# updateMate.net
KiCad netlist of a schematic drawn in EAGLE
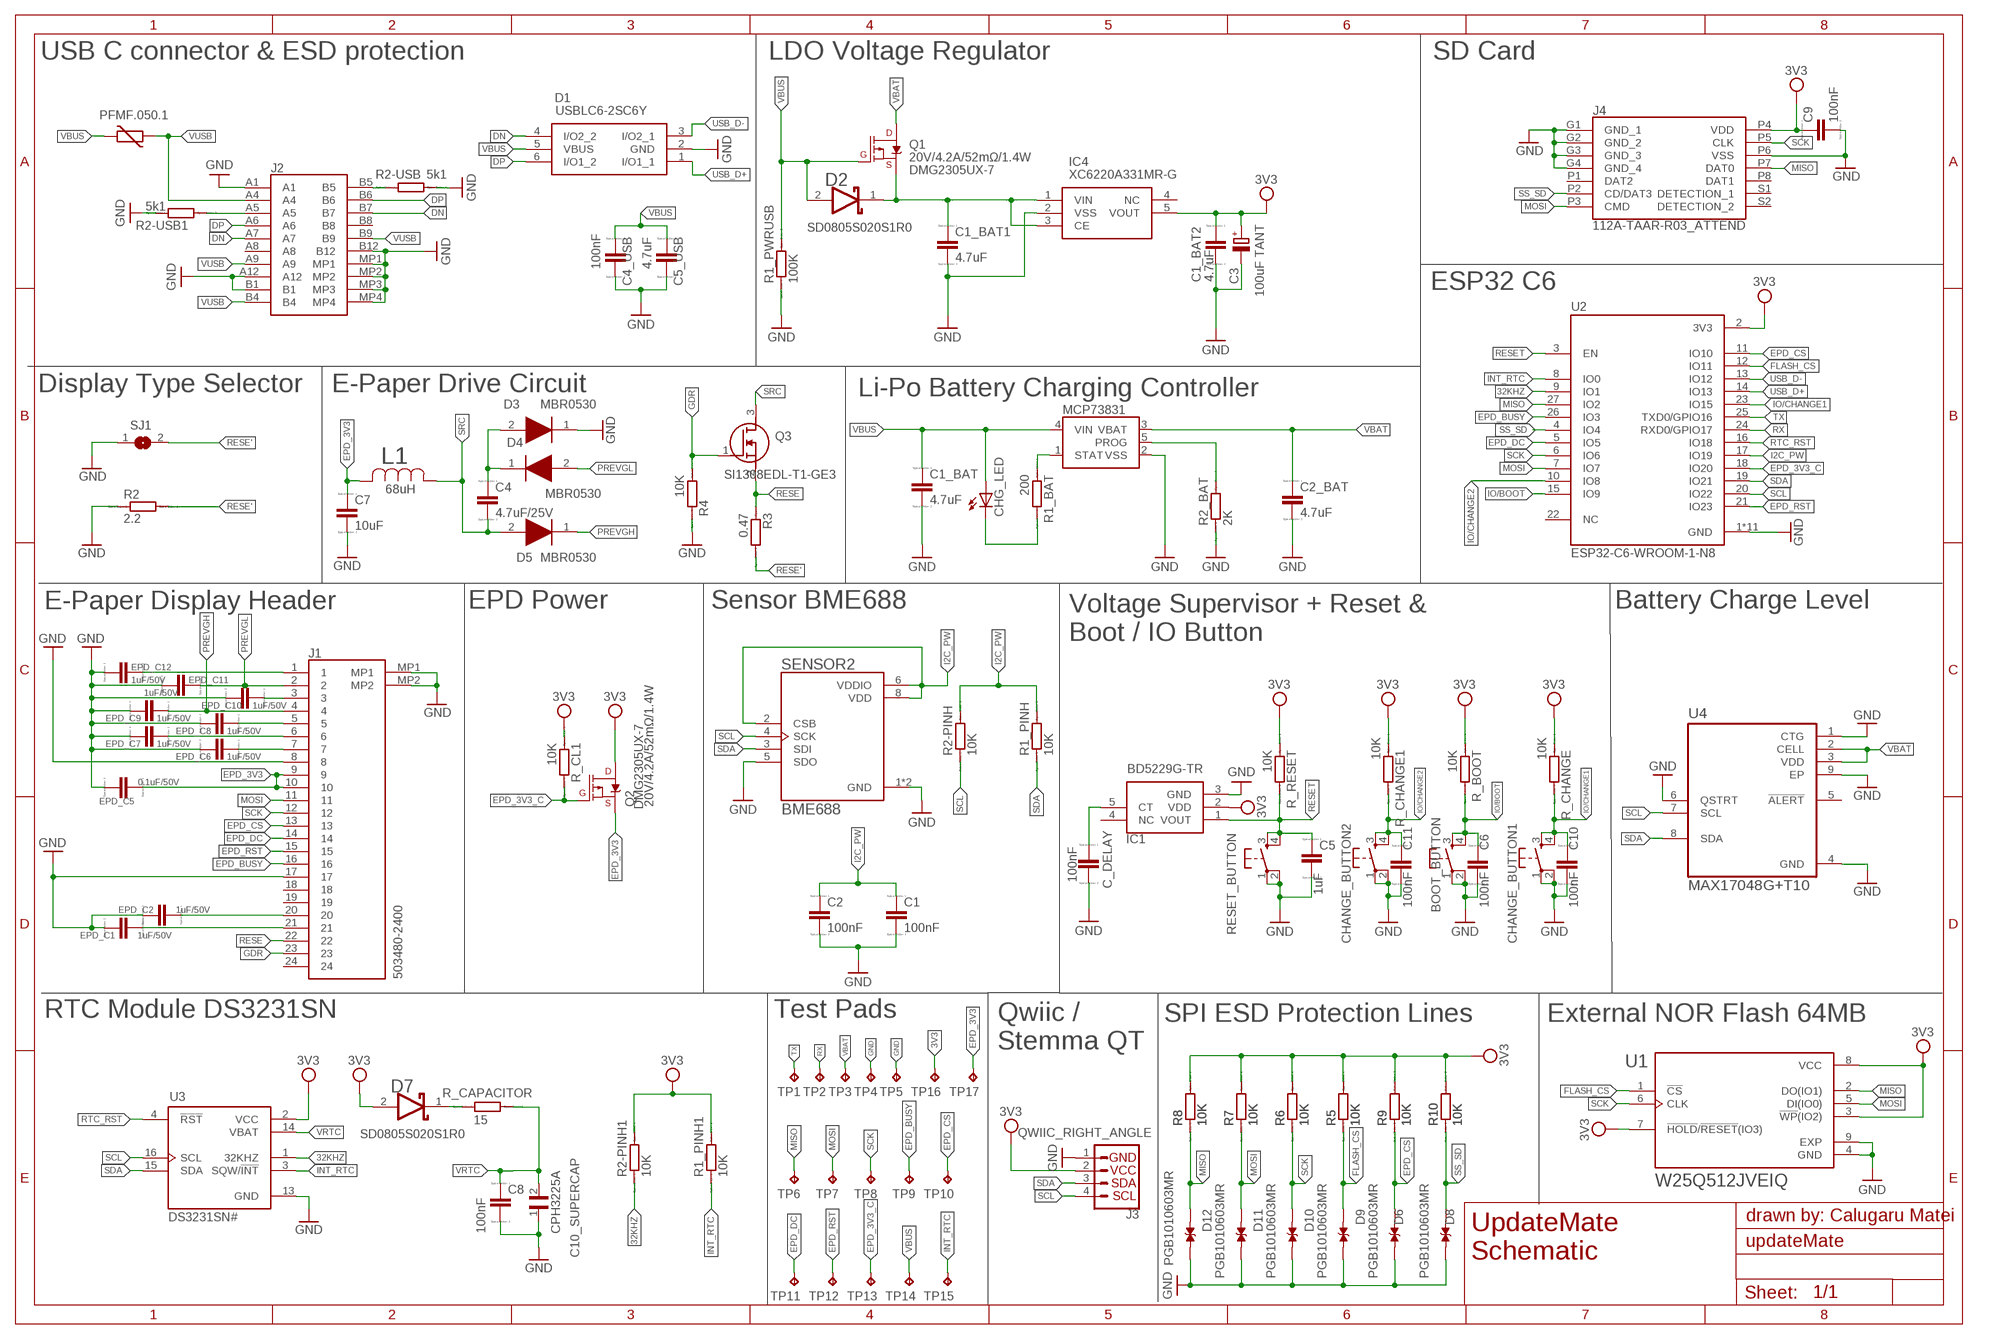
[diagram p0: schematic, sheet 1]

(export (version "E")
  (design (tool "Eeschema 10.0.6"))
  (components
    (comp (ref "BOOT_BUTTON")
      (value "BUTTON_CUSYOMV1")
      (footprint "eagle-import:MYBUTTON")
      (libsource (lib "eagle-import") (part "BUTTON_CUSYOMV1"))
    )
    (comp (ref "C1")
      (value "100nF")
      (footprint "eagle-import:ESP32_WROVER_EAGLE-LTSPICE_C0402")
      (libsource (lib "eagle-import") (part "ESP32_WROVER_EAGLE-LTSPICE_CC0402"))
    )
    (comp (ref "C1_BAT")
      (value "4.7uF")
      (footprint "eagle-import:ESP32_WROVER_EAGLE-LTSPICE_C0402")
      (libsource (lib "eagle-import") (part "ESP32_WROVER_EAGLE-LTSPICE_CC0402"))
    )
    (comp (ref "C1_BAT1")
      (value "4.7uF")
      (footprint "eagle-import:ESP32_WROVER_EAGLE-LTSPICE_C0402")
      (libsource (lib "eagle-import") (part "ESP32_WROVER_EAGLE-LTSPICE_CC0402"))
    )
    (comp (ref "C1_BAT2")
      (value "4.7uF")
      (footprint "eagle-import:ESP32_WROVER_EAGLE-LTSPICE_C0402")
      (libsource (lib "eagle-import") (part "ESP32_WROVER_EAGLE-LTSPICE_CC0402"))
    )
    (comp (ref "C2")
      (value "100nF")
      (footprint "eagle-import:ESP32_WROVER_EAGLE-LTSPICE_C0402")
      (libsource (lib "eagle-import") (part "ESP32_WROVER_EAGLE-LTSPICE_CC0402"))
    )
    (comp (ref "C2_BAT")
      (value "4.7uF")
      (footprint "eagle-import:ESP32_WROVER_EAGLE-LTSPICE_C0402")
      (libsource (lib "eagle-import") (part "ESP32_WROVER_EAGLE-LTSPICE_CC0402"))
    )
    (comp (ref "C3")
      (value "100uF TANT")
      (footprint "eagle-import:RCL_CT3528")
      (libsource (lib "eagle-import") (part "RCL_CPOL-EUCT3528"))
    )
    (comp (ref "C4")
      (value "4.7uF/25V")
      (footprint "eagle-import:ESP32_WROVER_EAGLE-LTSPICE_C0402")
      (libsource (lib "eagle-import") (part "ESP32_WROVER_EAGLE-LTSPICE_CC0402"))
    )
    (comp (ref "C4_USB")
      (value "100nF")
      (footprint "eagle-import:ESP32_WROVER_EAGLE-LTSPICE_C0402")
      (libsource (lib "eagle-import") (part "ESP32_WROVER_EAGLE-LTSPICE_CC0402"))
    )
    (comp (ref "C5")
      (value "1uF")
      (footprint "eagle-import:ESP32_WROVER_EAGLE-LTSPICE_C0402")
      (libsource (lib "eagle-import") (part "ESP32_WROVER_EAGLE-LTSPICE_CC0402"))
    )
    (comp (ref "C5_USB")
      (value "4.7uF")
      (footprint "eagle-import:ESP32_WROVER_EAGLE-LTSPICE_C0402")
      (libsource (lib "eagle-import") (part "ESP32_WROVER_EAGLE-LTSPICE_CC0402"))
    )
    (comp (ref "C6")
      (value "100nF")
      (footprint "eagle-import:ESP32_WROVER_EAGLE-LTSPICE_C0402")
      (libsource (lib "eagle-import") (part "ESP32_WROVER_EAGLE-LTSPICE_CC0402"))
    )
    (comp (ref "C7")
      (value "10uF")
      (footprint "eagle-import:ESP32_WROVER_EAGLE-LTSPICE_C0402")
      (libsource (lib "eagle-import") (part "ESP32_WROVER_EAGLE-LTSPICE_CC0402"))
    )
    (comp (ref "C8")
      (value "100nF")
      (footprint "eagle-import:ESP32_WROVER_EAGLE-LTSPICE_C0402")
      (libsource (lib "eagle-import") (part "ESP32_WROVER_EAGLE-LTSPICE_CC0402"))
    )
    (comp (ref "C9")
      (value "100nF")
      (footprint "eagle-import:EAGLE-LTSPICE_C0402")
      (libsource (lib "eagle-import") (part "EAGLE-LTSPICE_CC0402"))
    )
    (comp (ref "C10")
      (value "100nF")
      (footprint "eagle-import:ESP32_WROVER_EAGLE-LTSPICE_C0402")
      (libsource (lib "eagle-import") (part "ESP32_WROVER_EAGLE-LTSPICE_CC0402"))
    )
    (comp (ref "C10_SUPERCAP")
      (value "CPH3225A")
      (footprint "eagle-import:CAPCP3225X100N")
      (fields (field (name "MF") "Seiko Instruments"))
      (libsource (lib "eagle-import") (part "CPH3225A"))
    )
    (comp (ref "C11")
      (value "100nF")
      (footprint "eagle-import:ESP32_WROVER_EAGLE-LTSPICE_C0402")
      (libsource (lib "eagle-import") (part "ESP32_WROVER_EAGLE-LTSPICE_CC0402"))
    )
    (comp (ref "CHANGE_BUTTON1")
      (value "BUTTON_CUSYOMV1")
      (footprint "eagle-import:MYBUTTON")
      (libsource (lib "eagle-import") (part "BUTTON_CUSYOMV1"))
    )
    (comp (ref "CHANGE_BUTTON2")
      (value "BUTTON_CUSYOMV1")
      (footprint "eagle-import:MYBUTTON")
      (libsource (lib "eagle-import") (part "BUTTON_CUSYOMV1"))
    )
    (comp (ref "CHG_LED")
      (value "ADAFRUIT_LEDCHIP-LED0603")
      (footprint "eagle-import:ADAFRUIT_CHIP-LED0603")
      (libsource (lib "eagle-import") (part "ADAFRUIT_LEDCHIP-LED0603"))
    )
    (comp (ref "C_DELAY")
      (value "100nF")
      (footprint "eagle-import:ESP32_WROVER_EAGLE-LTSPICE_C0402")
      (libsource (lib "eagle-import") (part "ESP32_WROVER_EAGLE-LTSPICE_CC0402"))
    )
    (comp (ref "D1")
      (value "USBLC6-2SC6Y")
      (footprint "eagle-import:SOT95P280X145-6N")
      (fields (field (name "MF") "STMicroelectronics"))
      (libsource (lib "eagle-import") (part "USBLC6-2SC6Y"))
    )
    (comp (ref "D2")
      (value "ESP32_WROVER_AVX---SD0805S020S1R0_AVX_SD0805S020S1R0AVX_SD0805S020S1R0_0_0")
      (footprint "eagle-import:ESP32_WROVER_AVX---SD0805S020S1R0_AVX_SD0805S020S1R0_0")
      (fields
        (field (name "DIGIKEY_PART_NUMBER") "478-7800-1-ND")
        (field (name "MF") "AVX")
        (field (name "MOUSER_PART_NUMBER") "581-SD0805S020S1R0")
      )
      (libsource (lib "eagle-import") (part "ESP32_WROVER_AVX---SD0805S020S1R0_AVX_SD0805S020S1R0_0_0AVX_SD0805S020S1R0_0_0"))
    )
    (comp (ref "D3")
      (value "MBR0530")
      (footprint "eagle-import:SOD3716X135N")
      (fields (field (name "MF") "ON Semiconductor"))
      (libsource (lib "eagle-import") (part "MBR0530"))
    )
    (comp (ref "D4")
      (value "MBR0530")
      (footprint "eagle-import:SOD3716X135N")
      (fields (field (name "MF") "ON Semiconductor"))
      (libsource (lib "eagle-import") (part "MBR0530"))
    )
    (comp (ref "D5")
      (value "MBR0530")
      (footprint "eagle-import:SOD3716X135N")
      (fields (field (name "MF") "ON Semiconductor"))
      (libsource (lib "eagle-import") (part "MBR0530"))
    )
    (comp (ref "D6")
      (value "PGB1010603MR")
      (footprint "eagle-import:DIOC1608X36N")
      (fields (field (name "MF") "Littelfuse Inc."))
      (libsource (lib "eagle-import") (part "PGB1010603MR"))
    )
    (comp (ref "D7")
      (value "SD0805S020S1R0")
      (footprint "eagle-import:ESP32_WROVER_AVX---SD0805S020S1R0_AVX_SD0805S020S1R0_0")
      (fields
        (field (name "DIGIKEY_PART_NUMBER") "478-7800-1-ND")
        (field (name "MF") "AVX")
        (field (name "MOUSER_PART_NUMBER") "581-SD0805S020S1R0")
      )
      (libsource (lib "eagle-import") (part "ESP32_WROVER_AVX---SD0805S020S1R0_AVX_SD0805S020S1R0_0_0AVX_SD0805S020S1R0_0_0"))
    )
    (comp (ref "D8")
      (value "PGB1010603MR")
      (footprint "eagle-import:DIOC1608X36N")
      (fields (field (name "MF") "Littelfuse Inc."))
      (libsource (lib "eagle-import") (part "PGB1010603MR"))
    )
    (comp (ref "D9")
      (value "PGB1010603MR")
      (footprint "eagle-import:DIOC1608X36N")
      (fields (field (name "MF") "Littelfuse Inc."))
      (libsource (lib "eagle-import") (part "PGB1010603MR"))
    )
    (comp (ref "D10")
      (value "PGB1010603MR")
      (footprint "eagle-import:DIOC1608X36N")
      (fields (field (name "MF") "Littelfuse Inc."))
      (libsource (lib "eagle-import") (part "PGB1010603MR"))
    )
    (comp (ref "D11")
      (value "PGB1010603MR")
      (footprint "eagle-import:DIOC1608X36N")
      (fields (field (name "MF") "Littelfuse Inc."))
      (libsource (lib "eagle-import") (part "PGB1010603MR"))
    )
    (comp (ref "D12")
      (value "PGB1010603MR")
      (footprint "eagle-import:DIOC1608X36N")
      (fields (field (name "MF") "Littelfuse Inc."))
      (libsource (lib "eagle-import") (part "PGB1010603MR"))
    )
    (comp (ref "EPD_C1")
      (value "1uF/50V")
      (footprint "eagle-import:ESP32_WROVER_EAGLE-LTSPICE_C0402")
      (libsource (lib "eagle-import") (part "ESP32_WROVER_EAGLE-LTSPICE_CC0402"))
    )
    (comp (ref "EPD_C2")
      (value "1uF/50V")
      (footprint "eagle-import:ESP32_WROVER_EAGLE-LTSPICE_C0402")
      (libsource (lib "eagle-import") (part "ESP32_WROVER_EAGLE-LTSPICE_CC0402"))
    )
    (comp (ref "EPD_C5")
      (value "0.1uF/50V")
      (footprint "eagle-import:ESP32_WROVER_EAGLE-LTSPICE_C0402")
      (libsource (lib "eagle-import") (part "ESP32_WROVER_EAGLE-LTSPICE_CC0402"))
    )
    (comp (ref "EPD_C6")
      (value "1uF/50V")
      (footprint "eagle-import:ESP32_WROVER_EAGLE-LTSPICE_C0402")
      (libsource (lib "eagle-import") (part "ESP32_WROVER_EAGLE-LTSPICE_CC0402"))
    )
    (comp (ref "EPD_C7")
      (value "1uF/50V")
      (footprint "eagle-import:ESP32_WROVER_EAGLE-LTSPICE_C0402")
      (libsource (lib "eagle-import") (part "ESP32_WROVER_EAGLE-LTSPICE_CC0402"))
    )
    (comp (ref "EPD_C8")
      (value "1uF/50V")
      (footprint "eagle-import:ESP32_WROVER_EAGLE-LTSPICE_C0402")
      (libsource (lib "eagle-import") (part "ESP32_WROVER_EAGLE-LTSPICE_CC0402"))
    )
    (comp (ref "EPD_C9")
      (value "1uF/50V")
      (footprint "eagle-import:ESP32_WROVER_EAGLE-LTSPICE_C0402")
      (libsource (lib "eagle-import") (part "ESP32_WROVER_EAGLE-LTSPICE_CC0402"))
    )
    (comp (ref "EPD_C10")
      (value "1uF/50V")
      (footprint "eagle-import:ESP32_WROVER_EAGLE-LTSPICE_C0402")
      (libsource (lib "eagle-import") (part "ESP32_WROVER_EAGLE-LTSPICE_CC0402"))
    )
    (comp (ref "EPD_C11")
      (value "1uF/50V")
      (footprint "eagle-import:ESP32_WROVER_EAGLE-LTSPICE_C0402")
      (libsource (lib "eagle-import") (part "ESP32_WROVER_EAGLE-LTSPICE_CC0402"))
    )
    (comp (ref "EPD_C12")
      (value "1uF/50V")
      (footprint "eagle-import:ESP32_WROVER_EAGLE-LTSPICE_C0402")
      (libsource (lib "eagle-import") (part "ESP32_WROVER_EAGLE-LTSPICE_CC0402"))
    )
    (comp (ref "IC1")
      (value "BD5229G-TR")
      (footprint "eagle-import:SOT95P280X125-5N")
      (fields (field (name "MOUSER_PART_NUMBER") "755-BD5229G-TR"))
      (libsource (lib "eagle-import") (part "BD5229G-TR"))
    )
    (comp (ref "IC4")
      (value "XC6220A331MR-G")
      (footprint "eagle-import:SOT95P280X120-5N")
      (fields (field (name "MOUSER_PART_NUMBER") "865-XC6220A331MR-G"))
      (libsource (lib "eagle-import") (part "XC6220A331MR-G"))
    )
    (comp (ref "J1")
      (value "503480-2400")
      (footprint "eagle-import:5034802400")
      (fields (field (name "MOUSER_PART_NUMBER") "538-503480-2400"))
      (libsource (lib "eagle-import") (part "503480-2400"))
    )
    (comp (ref "J2")
      (value "SAMACSYS_PARTS_USB4110-GF-A")
      (footprint "eagle-import:SAMACSYS_PARTS_USB4110GFA")
      (fields
        (field (name "MANUFACTURER_PART_NUMBER") "USB4110-GF-A")
        (field (name "MOUSER_PART_NUMBER") "640-USB4110-GF-A")
      )
      (libsource (lib "eagle-import") (part "SAMACSYS_PARTS_USB4110-GF-A"))
    )
    (comp (ref "J3")
      (value "QWIIC_RIGHT_ANGLE")
      (footprint "eagle-import:JST04_1MM_RA")
      (libsource (lib "eagle-import") (part "QWIIC_CONNECTORJS-1MM"))
    )
    (comp (ref "J4")
      (value "112A-TAAR-R03_ATTEND")
      (footprint "eagle-import:112ATAARR03ATTEND")
      (fields (field (name "MANUFACTURER_PART_NUMBER") "112A-TAAR-R03 ATTEND"))
      (libsource (lib "eagle-import") (part "112A-TAAR-R03_ATTEND"))
    )
    (comp (ref "L1")
      (value "68uH")
      (footprint "eagle-import:IND_4828-WE-TPC_WRE")
      (fields
        (field (name "MANUFACTURER_PART_NUMBER") "744043680")
        (field (name "COPYRIGHT") "Copyright (C) 2024 Ultra Librarian. All rights reserved.")
      )
      (libsource (lib "eagle-import") (part "744043680IND_4828-WE-TPC_WRE"))
    )
    (comp (ref "MCP73831")
      (value "ESP32_WROVER_SPARKFUN-IC-POWER_MCP73831")
      (footprint "eagle-import:ESP32_WROVER_SPARKFUN-IC-POWER_SOT23-5")
      (libsource (lib "eagle-import") (part "ESP32_WROVER_SPARKFUN-IC-POWER_MCP73831"))
    )
    (comp (ref "PFMF.050.1")
      (value "ESP32C6_VARISTORCN1812")
      (footprint "eagle-import:ESP32C6_VARISTOR_CT_CN1812")
      (libsource (lib "eagle-import") (part "ESP32C6_VARISTORCN1812"))
    )
    (comp (ref "Q1")
      (value "20V/4.2A/52mΩ/1.4W")
      (footprint "eagle-import:ESP32_WROVER_SPARKFUN-DISCRETESEMI_SOT23-3")
      (libsource (lib "eagle-import") (part "ESP32_WROVER_SPARKFUN-DISCRETESEMI_MOSFET_PCH-DMG2305UX-7"))
    )
    (comp (ref "Q2")
      (value "20V/4.2A/52mΩ/1.4W")
      (footprint "eagle-import:ESP32_WROVER_SPARKFUN-DISCRETESEMI_SOT23-3")
      (libsource (lib "eagle-import") (part "ESP32_WROVER_SPARKFUN-DISCRETESEMI_MOSFET_PCH-DMG2305UX-7"))
    )
    (comp (ref "Q3")
      (value "SI1308EDL-T1-GE3")
      (footprint "eagle-import:SOT65P210X110-3N")
      (fields (field (name "MF") "Vishay Siliconix"))
      (libsource (lib "eagle-import") (part "SI1308EDL-T1-GE3"))
    )
    (comp (ref "R1_BAT")
      (value "200")
      (footprint "eagle-import:ESP32_WROVER_EAGLE-LTSPICE_R0402")
      (libsource (lib "eagle-import") (part "ESP32_WROVER_EAGLE-LTSPICE_RR0402"))
    )
    (comp (ref "R1_PINH")
      (value "10K")
      (footprint "eagle-import:ESP32_WROVER_EAGLE-LTSPICE_R0402")
      (libsource (lib "eagle-import") (part "ESP32_WROVER_EAGLE-LTSPICE_RR0402"))
    )
    (comp (ref "R1_PINH1")
      (value "10K")
      (footprint "eagle-import:ESP32_WROVER_EAGLE-LTSPICE_R0402")
      (libsource (lib "eagle-import") (part "ESP32_WROVER_EAGLE-LTSPICE_RR0402"))
    )
    (comp (ref "R1_PWRUSB")
      (value "100K")
      (footprint "eagle-import:ESP32_WROVER_EAGLE-LTSPICE_R0402")
      (libsource (lib "eagle-import") (part "ESP32_WROVER_EAGLE-LTSPICE_RR0402"))
    )
    (comp (ref "R2")
      (value "2.2")
      (footprint "eagle-import:ESP32_WROVER_EAGLE-LTSPICE_R0402")
      (libsource (lib "eagle-import") (part "ESP32_WROVER_EAGLE-LTSPICE_RR0402"))
    )
    (comp (ref "R2-PINH")
      (value "10K")
      (footprint "eagle-import:ESP32_WROVER_EAGLE-LTSPICE_R0402")
      (libsource (lib "eagle-import") (part "ESP32_WROVER_EAGLE-LTSPICE_RR0402"))
    )
    (comp (ref "R2-PINH1")
      (value "10K")
      (footprint "eagle-import:ESP32_WROVER_EAGLE-LTSPICE_R0402")
      (libsource (lib "eagle-import") (part "ESP32_WROVER_EAGLE-LTSPICE_RR0402"))
    )
    (comp (ref "R2-USB")
      (value "5k1")
      (footprint "eagle-import:ESP32_WROVER_EAGLE-LTSPICE_R0402")
      (libsource (lib "eagle-import") (part "ESP32_WROVER_EAGLE-LTSPICE_RR0402"))
    )
    (comp (ref "R2-USB1")
      (value "5k1")
      (footprint "eagle-import:ESP32_WROVER_EAGLE-LTSPICE_R0402")
      (libsource (lib "eagle-import") (part "ESP32_WROVER_EAGLE-LTSPICE_RR0402"))
    )
    (comp (ref "R2_BAT")
      (value "2K")
      (footprint "eagle-import:ESP32_WROVER_EAGLE-LTSPICE_R0402")
      (libsource (lib "eagle-import") (part "ESP32_WROVER_EAGLE-LTSPICE_RR0402"))
    )
    (comp (ref "R3")
      (value "0.47")
      (footprint "eagle-import:ESP32_WROVER_EAGLE-LTSPICE_R0402")
      (libsource (lib "eagle-import") (part "ESP32_WROVER_EAGLE-LTSPICE_RR0402"))
    )
    (comp (ref "R4")
      (value "10K")
      (footprint "eagle-import:ESP32_WROVER_EAGLE-LTSPICE_R0402")
      (libsource (lib "eagle-import") (part "ESP32_WROVER_EAGLE-LTSPICE_RR0402"))
    )
    (comp (ref "R5")
      (value "10K")
      (footprint "eagle-import:ESP32_WROVER_EAGLE-LTSPICE_R0402")
      (libsource (lib "eagle-import") (part "ESP32_WROVER_EAGLE-LTSPICE_RR0402"))
    )
    (comp (ref "R6")
      (value "10K")
      (footprint "eagle-import:ESP32_WROVER_EAGLE-LTSPICE_R0402")
      (libsource (lib "eagle-import") (part "ESP32_WROVER_EAGLE-LTSPICE_RR0402"))
    )
    (comp (ref "R7")
      (value "10K")
      (footprint "eagle-import:ESP32_WROVER_EAGLE-LTSPICE_R0402")
      (libsource (lib "eagle-import") (part "ESP32_WROVER_EAGLE-LTSPICE_RR0402"))
    )
    (comp (ref "R8")
      (value "10K")
      (footprint "eagle-import:ESP32_WROVER_EAGLE-LTSPICE_R0402")
      (libsource (lib "eagle-import") (part "ESP32_WROVER_EAGLE-LTSPICE_RR0402"))
    )
    (comp (ref "R9")
      (value "10K")
      (footprint "eagle-import:ESP32_WROVER_EAGLE-LTSPICE_R0402")
      (libsource (lib "eagle-import") (part "ESP32_WROVER_EAGLE-LTSPICE_RR0402"))
    )
    (comp (ref "R10")
      (value "10K")
      (footprint "eagle-import:ESP32_WROVER_EAGLE-LTSPICE_R0402")
      (libsource (lib "eagle-import") (part "ESP32_WROVER_EAGLE-LTSPICE_RR0402"))
    )
    (comp (ref "RESET_BUTTON")
      (value "BUTTON_CUSYOMV1")
      (footprint "eagle-import:MYBUTTON")
      (libsource (lib "eagle-import") (part "BUTTON_CUSYOMV1"))
    )
    (comp (ref "R_BOOT")
      (value "10K")
      (footprint "eagle-import:ESP32_WROVER_EAGLE-LTSPICE_R0402")
      (libsource (lib "eagle-import") (part "ESP32_WROVER_EAGLE-LTSPICE_RR0402"))
    )
    (comp (ref "R_CAPACITOR")
      (value "15")
      (footprint "eagle-import:ESP32_WROVER_EAGLE-LTSPICE_R0402")
      (libsource (lib "eagle-import") (part "ESP32_WROVER_EAGLE-LTSPICE_RR0402"))
    )
    (comp (ref "R_CHANGE")
      (value "10K")
      (footprint "eagle-import:ESP32_WROVER_EAGLE-LTSPICE_R0402")
      (libsource (lib "eagle-import") (part "ESP32_WROVER_EAGLE-LTSPICE_RR0402"))
    )
    (comp (ref "R_CHANGE1")
      (value "10K")
      (footprint "eagle-import:ESP32_WROVER_EAGLE-LTSPICE_R0402")
      (libsource (lib "eagle-import") (part "ESP32_WROVER_EAGLE-LTSPICE_RR0402"))
    )
    (comp (ref "R_CL1")
      (value "10K")
      (footprint "eagle-import:ESP32_WROVER_EAGLE-LTSPICE_R0402")
      (libsource (lib "eagle-import") (part "ESP32_WROVER_EAGLE-LTSPICE_RR0402"))
    )
    (comp (ref "R_RESET")
      (value "10K")
      (footprint "eagle-import:ESP32_WROVER_EAGLE-LTSPICE_R0402")
      (libsource (lib "eagle-import") (part "ESP32_WROVER_EAGLE-LTSPICE_RR0402"))
    )
    (comp (ref "SENSOR2")
      (value "BME688")
      (footprint "eagle-import:ESP32_WROVER_BME680_PSON80P300X300X100-8N")
      (fields (field (name "MF") "Bosch Sensortec") (field (name "MP") "BME680"))
      (libsource (lib "eagle-import") (part "ESP32_WROVER_BME680_BME680"))
    )
    (comp (ref "SJ1") (value "SJ") (footprint "eagle-import:SJ") (libsource (lib "eagle-import") (part "SJ")))
    (comp (ref "TP1")
      (value "TPTP20R")
      (footprint "eagle-import:TP20R")
      (libsource (lib "eagle-import") (part "TPTP20R"))
    )
    (comp (ref "TP2")
      (value "TPTP20R")
      (footprint "eagle-import:TP20R")
      (libsource (lib "eagle-import") (part "TPTP20R"))
    )
    (comp (ref "TP3")
      (value "TPTP20R")
      (footprint "eagle-import:TP20R")
      (libsource (lib "eagle-import") (part "TPTP20R"))
    )
    (comp (ref "TP4")
      (value "TPTP20R")
      (footprint "eagle-import:TP20R")
      (libsource (lib "eagle-import") (part "TPTP20R"))
    )
    (comp (ref "TP5")
      (value "TPTP20R")
      (footprint "eagle-import:TP20R")
      (libsource (lib "eagle-import") (part "TPTP20R"))
    )
    (comp (ref "TP6")
      (value "TPTP20R")
      (footprint "eagle-import:TP20R")
      (libsource (lib "eagle-import") (part "TPTP20R"))
    )
    (comp (ref "TP7")
      (value "TPTP20R")
      (footprint "eagle-import:TP20R")
      (libsource (lib "eagle-import") (part "TPTP20R"))
    )
    (comp (ref "TP8")
      (value "TPTP20R")
      (footprint "eagle-import:TP20R")
      (libsource (lib "eagle-import") (part "TPTP20R"))
    )
    (comp (ref "TP9")
      (value "TPTP20R")
      (footprint "eagle-import:TP20R")
      (libsource (lib "eagle-import") (part "TPTP20R"))
    )
    (comp (ref "TP10")
      (value "TPTP20R")
      (footprint "eagle-import:TP20R")
      (libsource (lib "eagle-import") (part "TPTP20R"))
    )
    (comp (ref "TP11")
      (value "TPTP20R")
      (footprint "eagle-import:TP20R")
      (libsource (lib "eagle-import") (part "TPTP20R"))
    )
    (comp (ref "TP12")
      (value "TPTP20R")
      (footprint "eagle-import:TP20R")
      (libsource (lib "eagle-import") (part "TPTP20R"))
    )
    (comp (ref "TP13")
      (value "TPTP20R")
      (footprint "eagle-import:TP20R")
      (libsource (lib "eagle-import") (part "TPTP20R"))
    )
    (comp (ref "TP14")
      (value "TPTP20R")
      (footprint "eagle-import:TP20R")
      (libsource (lib "eagle-import") (part "TPTP20R"))
    )
    (comp (ref "TP15")
      (value "TPTP20R")
      (footprint "eagle-import:TP20R")
      (libsource (lib "eagle-import") (part "TPTP20R"))
    )
    (comp (ref "TP16")
      (value "TPTP20R")
      (footprint "eagle-import:TP20R")
      (libsource (lib "eagle-import") (part "TPTP20R"))
    )
    (comp (ref "TP17")
      (value "TPTP20R")
      (footprint "eagle-import:TP20R")
      (libsource (lib "eagle-import") (part "TPTP20R"))
    )
    (comp (ref "U1")
      (value "W25Q512JVEIQ")
      (footprint "eagle-import:SON127P600X800X80-9N")
      (fields (field (name "MF") "Winbond Electronics"))
      (libsource (lib "eagle-import") (part "W25Q512JVEIQ"))
    )
    (comp (ref "U2")
      (value "ESP32-C6-WROOM-1-N8")
      (footprint "eagle-import:XCVR_ESP32-C6-WROOM-1-N8")
      (fields (field (name "MF") "Espressif Systems"))
      (libsource (lib "eagle-import") (part "ESP32-C6-WROOM-1-N8"))
    )
    (comp (ref "U3")
      (value "DS3231SN#")
      (footprint "eagle-import:SOIC127P1032X265-16N")
      (fields (field (name "MF") "Analog Devices"))
      (libsource (lib "eagle-import") (part "DS3231SN#"))
    )
    (comp (ref "U4")
      (value "MAX17048G+T10")
      (footprint "eagle-import:SON50P200X200X80-9N")
      (fields (field (name "MF") "Analog Devices"))
      (libsource (lib "eagle-import") (part "MAX17048G+T10"))
    )
  )
  (nets
    (net (code "1") (name "3V3") (class "Default")
      (node (ref "C1_BAT2") (pin "1") (pinfunction "1_1") (pintype "passive"))
      (node (ref "C3") (pin "+") (pinfunction "+_+") (pintype "passive"))
      (node (ref "C9") (pin "1") (pinfunction "1_1") (pintype "passive"))
      (node (ref "D7") (pin "2") (pinfunction "ANODE_2") (pintype "bidirectional"))
      (node (ref "IC1") (pin "2") (pinfunction "VDD_2") (pintype "bidirectional"))
      (node (ref "IC4") (pin "5") (pinfunction "VOUT_5") (pintype "bidirectional"))
      (node (ref "J3") (pin "2") (pinfunction "2_2") (pintype "power_in"))
      (node (ref "J4") (pin "P4") (pinfunction "VDD_P4") (pintype "bidirectional"))
      (node (ref "Q2") (pin "3") (pinfunction "D_3") (pintype "bidirectional"))
      (node (ref "R10") (pin "2") (pinfunction "2_2") (pintype "passive"))
      (node (ref "R1_PINH1") (pin "2") (pinfunction "2_2") (pintype "passive"))
      (node (ref "R2-PINH1") (pin "2") (pinfunction "2_2") (pintype "passive"))
      (node (ref "R5") (pin "2") (pinfunction "2_2") (pintype "passive"))
      (node (ref "R6") (pin "2") (pinfunction "2_2") (pintype "passive"))
      (node (ref "R7") (pin "2") (pinfunction "2_2") (pintype "passive"))
      (node (ref "R8") (pin "2") (pinfunction "2_2") (pintype "passive"))
      (node (ref "R9") (pin "2") (pinfunction "2_2") (pintype "passive"))
      (node (ref "R_BOOT") (pin "1") (pinfunction "1_1") (pintype "passive"))
      (node (ref "R_CHANGE") (pin "1") (pinfunction "1_1") (pintype "passive"))
      (node (ref "R_CHANGE1") (pin "1") (pinfunction "1_1") (pintype "passive"))
      (node (ref "R_CL1") (pin "1") (pinfunction "1_1") (pintype "passive"))
      (node (ref "R_RESET") (pin "1") (pinfunction "1_1") (pintype "passive"))
      (node (ref "TP16") (pin "TP") (pinfunction "TP_TP") (pintype "input"))
      (node (ref "U1") (pin "3") (pinfunction "~{WP}(IO2)_3") (pintype "bidirectional"))
      (node (ref "U1") (pin "7") (pinfunction "~{HOLD}/~{RESET}(IO3)_7") (pintype "bidirectional"))
      (node (ref "U1") (pin "8") (pinfunction "VCC_8") (pintype "power_in"))
      (node (ref "U2") (pin "2") (pinfunction "3V3_2") (pintype "power_in"))
      (node (ref "U3") (pin "2") (pinfunction "VCC_2") (pintype "power_in"))
    )
    (net (code "2") (name "32KHZ") (class "Default")
      (node (ref "R2-PINH1") (pin "1") (pinfunction "1_1") (pintype "passive"))
      (node (ref "U2") (pin "9") (pinfunction "IO1_9") (pintype "bidirectional"))
      (node (ref "U3") (pin "1") (pinfunction "32KHZ_1") (pintype "output"))
    )
    (net (code "3") (name "DN") (class "Default")
      (node (ref "D1") (pin "4") (pinfunction "I/O2_2_4") (pintype "bidirectional"))
      (node (ref "J2") (pin "A7") (pinfunction "A7_A7") (pintype "bidirectional"))
      (node (ref "J2") (pin "B7") (pinfunction "B7_B7") (pintype "bidirectional"))
    )
    (net (code "4") (name "DP") (class "Default")
      (node (ref "D1") (pin "6") (pinfunction "I/O1_2_6") (pintype "bidirectional"))
      (node (ref "J2") (pin "A6") (pinfunction "A6_A6") (pintype "bidirectional"))
      (node (ref "J2") (pin "B6") (pinfunction "B6_B6") (pintype "bidirectional"))
    )
    (net (code "5") (name "EPD_3V3") (class "Default")
      (node (ref "C7") (pin "1") (pinfunction "1_1") (pintype "passive"))
      (node (ref "EPD_C5") (pin "1") (pinfunction "1_1") (pintype "passive"))
      (node (ref "J1") (pin "10") (pinfunction "10_10") (pintype "bidirectional"))
      (node (ref "J1") (pin "9") (pinfunction "9_9") (pintype "bidirectional"))
      (node (ref "L1") (pin "2") (pinfunction "2_2") (pintype "passive"))
      (node (ref "Q2") (pin "2") (pinfunction "S_2") (pintype "bidirectional"))
      (node (ref "TP17") (pin "TP") (pinfunction "TP_TP") (pintype "input"))
    )
    (net (code "6") (name "EPD_3V3_C") (class "Default")
      (node (ref "Q2") (pin "1") (pinfunction "G_1") (pintype "bidirectional"))
      (node (ref "R_CL1") (pin "2") (pinfunction "2_2") (pintype "passive"))
      (node (ref "TP13") (pin "TP") (pinfunction "TP_TP") (pintype "input"))
      (node (ref "U2") (pin "18") (pinfunction "IO20_18") (pintype "bidirectional"))
    )
    (net (code "7") (name "EPD_BUSY") (class "Default")
      (node (ref "J1") (pin "16") (pinfunction "16_16") (pintype "bidirectional"))
      (node (ref "TP9") (pin "TP") (pinfunction "TP_TP") (pintype "input"))
      (node (ref "U2") (pin "26") (pinfunction "IO3_26") (pintype "bidirectional"))
    )
    (net (code "8") (name "EPD_CS") (class "Default")
      (node (ref "D6") (pin "1") (pinfunction "1_1") (pintype "passive"))
      (node (ref "J1") (pin "13") (pinfunction "13_13") (pintype "bidirectional"))
      (node (ref "R9") (pin "1") (pinfunction "1_1") (pintype "passive"))
      (node (ref "TP10") (pin "TP") (pinfunction "TP_TP") (pintype "input"))
      (node (ref "U2") (pin "11") (pinfunction "IO10_11") (pintype "bidirectional"))
    )
    (net (code "9") (name "EPD_DC") (class "Default")
      (node (ref "J1") (pin "14") (pinfunction "14_14") (pintype "bidirectional"))
      (node (ref "TP11") (pin "TP") (pinfunction "TP_TP") (pintype "input"))
      (node (ref "U2") (pin "5") (pinfunction "IO5_5") (pintype "bidirectional"))
    )
    (net (code "10") (name "EPD_RST") (class "Default")
      (node (ref "J1") (pin "15") (pinfunction "15_15") (pintype "bidirectional"))
      (node (ref "TP12") (pin "TP") (pinfunction "TP_TP") (pintype "input"))
      (node (ref "U2") (pin "21") (pinfunction "IO23_21") (pintype "bidirectional"))
    )
    (net (code "11") (name "FLASH_CS") (class "Default")
      (node (ref "D9") (pin "1") (pinfunction "1_1") (pintype "passive"))
      (node (ref "R5") (pin "1") (pinfunction "1_1") (pintype "passive"))
      (node (ref "U1") (pin "1") (pinfunction "~{CS}_1") (pintype "input"))
      (node (ref "U2") (pin "12") (pinfunction "IO11_12") (pintype "bidirectional"))
    )
    (net (code "12") (name "GDR") (class "Default")
      (node (ref "J1") (pin "23") (pinfunction "23_23") (pintype "bidirectional"))
      (node (ref "Q3") (pin "1") (pinfunction "G_1") (pintype "bidirectional"))
      (node (ref "R4") (pin "1") (pinfunction "1_1") (pintype "passive"))
    )
    (net (code "13") (name "GND") (class "Default")
      (node (ref "BOOT_BUTTON") (pin "1") (pinfunction "1_1") (pintype "passive"))
      (node (ref "BOOT_BUTTON") (pin "2") (pinfunction "2_2") (pintype "passive"))
      (node (ref "C1") (pin "2") (pinfunction "2_2") (pintype "passive"))
      (node (ref "C10") (pin "2") (pinfunction "2_2") (pintype "passive"))
      (node (ref "C10_SUPERCAP") (pin "1") (pinfunction "1_1") (pintype "passive"))
      (node (ref "C11") (pin "2") (pinfunction "2_2") (pintype "passive"))
      (node (ref "C1_BAT") (pin "2") (pinfunction "2_2") (pintype "passive"))
      (node (ref "C1_BAT1") (pin "2") (pinfunction "2_2") (pintype "passive"))
      (node (ref "C1_BAT2") (pin "2") (pinfunction "2_2") (pintype "passive"))
      (node (ref "C2") (pin "2") (pinfunction "2_2") (pintype "passive"))
      (node (ref "C2_BAT") (pin "2") (pinfunction "2_2") (pintype "passive"))
      (node (ref "C3") (pin "-") (pinfunction "-_-") (pintype "passive"))
      (node (ref "C4_USB") (pin "2") (pinfunction "2_2") (pintype "passive"))
      (node (ref "C5") (pin "2") (pinfunction "2_2") (pintype "passive"))
      (node (ref "C5_USB") (pin "2") (pinfunction "2_2") (pintype "passive"))
      (node (ref "C6") (pin "2") (pinfunction "2_2") (pintype "passive"))
      (node (ref "C7") (pin "2") (pinfunction "2_2") (pintype "passive"))
      (node (ref "C8") (pin "2") (pinfunction "2_2") (pintype "passive"))
      (node (ref "C9") (pin "2") (pinfunction "2_2") (pintype "passive"))
      (node (ref "CHANGE_BUTTON1") (pin "1") (pinfunction "1_1") (pintype "passive"))
      (node (ref "CHANGE_BUTTON1") (pin "2") (pinfunction "2_2") (pintype "passive"))
      (node (ref "CHANGE_BUTTON2") (pin "1") (pinfunction "1_1") (pintype "passive"))
      (node (ref "CHANGE_BUTTON2") (pin "2") (pinfunction "2_2") (pintype "passive"))
      (node (ref "C_DELAY") (pin "2") (pinfunction "2_2") (pintype "passive"))
      (node (ref "D1") (pin "2") (pinfunction "GND_2") (pintype "bidirectional"))
      (node (ref "D10") (pin "2") (pinfunction "2_2") (pintype "passive"))
      (node (ref "D11") (pin "2") (pinfunction "2_2") (pintype "passive"))
      (node (ref "D12") (pin "2") (pinfunction "2_2") (pintype "passive"))
      (node (ref "D3") (pin "1") (pinfunction "K_1") (pintype "bidirectional"))
      (node (ref "D6") (pin "2") (pinfunction "2_2") (pintype "passive"))
      (node (ref "D8") (pin "2") (pinfunction "2_2") (pintype "passive"))
      (node (ref "D9") (pin "2") (pinfunction "2_2") (pintype "passive"))
      (node (ref "EPD_C1") (pin "2") (pinfunction "2_2") (pintype "passive"))
      (node (ref "EPD_C10") (pin "2") (pinfunction "2_2") (pintype "passive"))
      (node (ref "EPD_C11") (pin "2") (pinfunction "2_2") (pintype "passive"))
      (node (ref "EPD_C12") (pin "2") (pinfunction "2_2") (pintype "passive"))
      (node (ref "EPD_C2") (pin "2") (pinfunction "2_2") (pintype "passive"))
      (node (ref "EPD_C5") (pin "2") (pinfunction "2_2") (pintype "passive"))
      (node (ref "EPD_C6") (pin "2") (pinfunction "2_2") (pintype "passive"))
      (node (ref "EPD_C7") (pin "2") (pinfunction "2_2") (pintype "passive"))
      (node (ref "EPD_C8") (pin "2") (pinfunction "2_2") (pintype "passive"))
      (node (ref "EPD_C9") (pin "2") (pinfunction "2_2") (pintype "passive"))
      (node (ref "IC1") (pin "3") (pinfunction "GND_3") (pintype "bidirectional"))
      (node (ref "IC4") (pin "2") (pinfunction "VSS_2") (pintype "bidirectional"))
      (node (ref "J1") (pin "17") (pinfunction "17_17") (pintype "bidirectional"))
      (node (ref "J1") (pin "8") (pinfunction "8_8") (pintype "bidirectional"))
      (node (ref "J1") (pin "MP1") (pinfunction "MP1_MP1") (pintype "bidirectional"))
      (node (ref "J1") (pin "MP2") (pinfunction "MP2_MP2") (pintype "bidirectional"))
      (node (ref "J2") (pin "A1") (pinfunction "A1_A1") (pintype "bidirectional"))
      (node (ref "J2") (pin "A12") (pinfunction "A12_A12") (pintype "bidirectional"))
      (node (ref "J2") (pin "B1") (pinfunction "B1_B1") (pintype "bidirectional"))
      (node (ref "J2") (pin "B12") (pinfunction "B12_B12") (pintype "bidirectional"))
      (node (ref "J2") (pin "MP1") (pinfunction "MP1_MP1") (pintype "bidirectional"))
      (node (ref "J2") (pin "MP2") (pinfunction "MP2_MP2") (pintype "bidirectional"))
      (node (ref "J2") (pin "MP3") (pinfunction "MP3_MP3") (pintype "bidirectional"))
      (node (ref "J2") (pin "MP4") (pinfunction "MP4_MP4") (pintype "bidirectional"))
      (node (ref "J3") (pin "1") (pinfunction "1_1") (pintype "power_in"))
      (node (ref "J4") (pin "G1") (pinfunction "GND_1_G1") (pintype "bidirectional"))
      (node (ref "J4") (pin "G2") (pinfunction "GND_2_G2") (pintype "bidirectional"))
      (node (ref "J4") (pin "G3") (pinfunction "GND_3_G3") (pintype "bidirectional"))
      (node (ref "J4") (pin "G4") (pinfunction "GND_4_G4") (pintype "bidirectional"))
      (node (ref "J4") (pin "P6") (pinfunction "VSS_P6") (pintype "bidirectional"))
      (node (ref "MCP73831") (pin "2") (pinfunction "VSS_2") (pintype "power_in"))
      (node (ref "R1_PWRUSB") (pin "1") (pinfunction "1_1") (pintype "passive"))
      (node (ref "R2") (pin "1") (pinfunction "1_1") (pintype "passive"))
      (node (ref "R2-USB") (pin "2") (pinfunction "2_2") (pintype "passive"))
      (node (ref "R2-USB1") (pin "1") (pinfunction "1_1") (pintype "passive"))
      (node (ref "R2_BAT") (pin "1") (pinfunction "1_1") (pintype "passive"))
      (node (ref "R4") (pin "2") (pinfunction "2_2") (pintype "passive"))
      (node (ref "RESET_BUTTON") (pin "1") (pinfunction "1_1") (pintype "passive"))
      (node (ref "RESET_BUTTON") (pin "2") (pinfunction "2_2") (pintype "passive"))
      (node (ref "SENSOR2") (pin "1") (pinfunction "GND_1") (pintype "power_in"))
      (node (ref "SENSOR2") (pin "5") (pinfunction "SDO_5") (pintype "bidirectional"))
      (node (ref "SENSOR2") (pin "7") (pinfunction "GND_7") (pintype "power_in"))
      (node (ref "SJ1") (pin "1") (pinfunction "1_1") (pintype "passive"))
      (node (ref "TP4") (pin "TP") (pinfunction "TP_TP") (pintype "input"))
      (node (ref "TP5") (pin "TP") (pinfunction "TP_TP") (pintype "input"))
      (node (ref "U1") (pin "4") (pinfunction "GND_4") (pintype "power_in"))
      (node (ref "U1") (pin "9") (pinfunction "EXP_9") (pintype "passive"))
      (node (ref "U2") (pin "1") (pinfunction "GND_1") (pintype "power_in"))
      (node (ref "U2") (pin "28") (pinfunction "GND_28") (pintype "power_in"))
      (node (ref "U2") (pin "29_1") (pinfunction "GND_29_1") (pintype "power_in"))
      (node (ref "U2") (pin "29_2") (pinfunction "GND_29_2") (pintype "power_in"))
      (node (ref "U2") (pin "29_3") (pinfunction "GND_29_3") (pintype "power_in"))
      (node (ref "U2") (pin "29_4") (pinfunction "GND_29_4") (pintype "power_in"))
      (node (ref "U2") (pin "29_5") (pinfunction "GND_29_5") (pintype "power_in"))
      (node (ref "U2") (pin "29_6") (pinfunction "GND_29_6") (pintype "power_in"))
      (node (ref "U2") (pin "29_7") (pinfunction "GND_29_7") (pintype "power_in"))
      (node (ref "U2") (pin "29_8") (pinfunction "GND_29_8") (pintype "power_in"))
      (node (ref "U2") (pin "29_9") (pinfunction "GND_29_9") (pintype "power_in"))
      (node (ref "U3") (pin "13") (pinfunction "GND_13") (pintype "power_in"))
      (node (ref "U4") (pin "1") (pinfunction "CTG_1") (pintype "power_in"))
      (node (ref "U4") (pin "4") (pinfunction "GND_4") (pintype "power_in"))
      (node (ref "U4") (pin "6") (pinfunction "QSTRT_6") (pintype "input"))
      (node (ref "U4") (pin "9") (pinfunction "EP_9") (pintype "power_in"))
    )
    (net (code "14") (name "I2C_PW") (class "Default")
      (node (ref "C1") (pin "1") (pinfunction "1_1") (pintype "passive"))
      (node (ref "C2") (pin "1") (pinfunction "1_1") (pintype "passive"))
      (node (ref "R1_PINH") (pin "2") (pinfunction "2_2") (pintype "passive"))
      (node (ref "R2-PINH") (pin "2") (pinfunction "2_2") (pintype "passive"))
      (node (ref "SENSOR2") (pin "2") (pinfunction "CSB_2") (pintype "input"))
      (node (ref "SENSOR2") (pin "6") (pinfunction "VDDIO_6") (pintype "power_in"))
      (node (ref "SENSOR2") (pin "8") (pinfunction "VDD_8") (pintype "power_in"))
      (node (ref "U2") (pin "17") (pinfunction "IO19_17") (pintype "bidirectional"))
    )
    (net (code "15") (name "INT_RTC") (class "Default")
      (node (ref "R1_PINH1") (pin "1") (pinfunction "1_1") (pintype "passive"))
      (node (ref "TP15") (pin "TP") (pinfunction "TP_TP") (pintype "input"))
      (node (ref "U2") (pin "8") (pinfunction "IO0_8") (pintype "bidirectional"))
      (node (ref "U3") (pin "3") (pinfunction "SQW/~{INT}_3") (pintype "output"))
    )
    (net (code "16") (name "IO{slash}BOOT") (class "Default")
      (node (ref "BOOT_BUTTON") (pin "3") (pinfunction "3_3") (pintype "passive"))
      (node (ref "BOOT_BUTTON") (pin "4") (pinfunction "4_4") (pintype "passive"))
      (node (ref "C6") (pin "1") (pinfunction "1_1") (pintype "passive"))
      (node (ref "R_BOOT") (pin "2") (pinfunction "2_2") (pintype "passive"))
      (node (ref "U2") (pin "15") (pinfunction "IO9_15") (pintype "bidirectional"))
    )
    (net (code "17") (name "IO{slash}CHANGE1") (class "Default")
      (node (ref "C10") (pin "1") (pinfunction "1_1") (pintype "passive"))
      (node (ref "CHANGE_BUTTON1") (pin "3") (pinfunction "3_3") (pintype "passive"))
      (node (ref "CHANGE_BUTTON1") (pin "4") (pinfunction "4_4") (pintype "passive"))
      (node (ref "R_CHANGE") (pin "2") (pinfunction "2_2") (pintype "passive"))
      (node (ref "U2") (pin "23") (pinfunction "IO15_23") (pintype "bidirectional"))
    )
    (net (code "18") (name "IO{slash}CHANGE2") (class "Default")
      (node (ref "C11") (pin "1") (pinfunction "1_1") (pintype "passive"))
      (node (ref "CHANGE_BUTTON2") (pin "3") (pinfunction "3_3") (pintype "passive"))
      (node (ref "CHANGE_BUTTON2") (pin "4") (pinfunction "4_4") (pintype "passive"))
      (node (ref "R_CHANGE1") (pin "2") (pinfunction "2_2") (pintype "passive"))
      (node (ref "U2") (pin "10") (pinfunction "IO8_10") (pintype "bidirectional"))
    )
    (net (code "19") (name "MISO") (class "Default")
      (node (ref "D12") (pin "1") (pinfunction "1_1") (pintype "passive"))
      (node (ref "J4") (pin "P7") (pinfunction "DAT0_P7") (pintype "bidirectional"))
      (node (ref "R8") (pin "1") (pinfunction "1_1") (pintype "passive"))
      (node (ref "TP6") (pin "TP") (pinfunction "TP_TP") (pintype "input"))
      (node (ref "U1") (pin "2") (pinfunction "DO(IO1)_2") (pintype "bidirectional"))
      (node (ref "U2") (pin "27") (pinfunction "IO2_27") (pintype "bidirectional"))
    )
    (net (code "20") (name "MOSI") (class "Default")
      (node (ref "D11") (pin "1") (pinfunction "1_1") (pintype "passive"))
      (node (ref "J1") (pin "11") (pinfunction "11_11") (pintype "bidirectional"))
      (node (ref "J4") (pin "P3") (pinfunction "CMD_P3") (pintype "bidirectional"))
      (node (ref "R7") (pin "1") (pinfunction "1_1") (pintype "passive"))
      (node (ref "TP7") (pin "TP") (pinfunction "TP_TP") (pintype "input"))
      (node (ref "U1") (pin "5") (pinfunction "DI(IO0)_5") (pintype "bidirectional"))
      (node (ref "U2") (pin "7") (pinfunction "IO7_7") (pintype "bidirectional"))
    )
    (net (code "21") (name "Net-(CHG_LED-PadC)") (class "Default")
      (node (ref "CHG_LED") (pin "C") (pinfunction "C_C") (pintype "passive"))
      (node (ref "R1_BAT") (pin "2") (pinfunction "2_2") (pintype "passive"))
    )
    (net (code "22") (name "Net-(D2-CATHODE)") (class "Default")
      (node (ref "C1_BAT1") (pin "1") (pinfunction "1_1") (pintype "passive"))
      (node (ref "D2") (pin "1") (pinfunction "CATHODE_1") (pintype "bidirectional"))
      (node (ref "IC4") (pin "1") (pinfunction "VIN_1") (pintype "bidirectional"))
      (node (ref "IC4") (pin "3") (pinfunction "CE_3") (pintype "bidirectional"))
      (node (ref "Q1") (pin "2") (pinfunction "S_2") (pintype "bidirectional"))
    )
    (net (code "23") (name "Net-(D3-A)") (class "Default")
      (node (ref "C4") (pin "1") (pinfunction "1_1") (pintype "passive"))
      (node (ref "D3") (pin "2") (pinfunction "A_2") (pintype "bidirectional"))
      (node (ref "D4") (pin "1") (pinfunction "K_1") (pintype "bidirectional"))
    )
    (net (code "24") (name "Net-(D7-CATHODE)") (class "Default")
      (node (ref "D7") (pin "1") (pinfunction "CATHODE_1") (pintype "bidirectional"))
      (node (ref "R_CAPACITOR") (pin "2") (pinfunction "2_2") (pintype "passive"))
    )
    (net (code "25") (name "Net-(EPD_C1-Pad1)") (class "Default")
      (node (ref "EPD_C1") (pin "1") (pinfunction "1_1") (pintype "passive"))
      (node (ref "J1") (pin "21") (pinfunction "21_21") (pintype "bidirectional"))
    )
    (net (code "26") (name "Net-(EPD_C2-Pad1)") (class "Default")
      (node (ref "EPD_C2") (pin "1") (pinfunction "1_1") (pintype "passive"))
      (node (ref "J1") (pin "20") (pinfunction "20_20") (pintype "bidirectional"))
    )
    (net (code "27") (name "Net-(EPD_C6-Pad1)") (class "Default")
      (node (ref "EPD_C6") (pin "1") (pinfunction "1_1") (pintype "passive"))
      (node (ref "J1") (pin "7") (pinfunction "7_7") (pintype "bidirectional"))
    )
    (net (code "28") (name "Net-(EPD_C7-Pad1)") (class "Default")
      (node (ref "EPD_C7") (pin "1") (pinfunction "1_1") (pintype "passive"))
      (node (ref "J1") (pin "6") (pinfunction "6_6") (pintype "bidirectional"))
    )
    (net (code "29") (name "Net-(EPD_C8-Pad1)") (class "Default")
      (node (ref "EPD_C8") (pin "1") (pinfunction "1_1") (pintype "passive"))
      (node (ref "J1") (pin "5") (pinfunction "5_5") (pintype "bidirectional"))
    )
    (net (code "30") (name "Net-(EPD_C10-Pad1)") (class "Default")
      (node (ref "EPD_C10") (pin "1") (pinfunction "1_1") (pintype "passive"))
      (node (ref "J1") (pin "3") (pinfunction "3_3") (pintype "bidirectional"))
    )
    (net (code "31") (name "Net-(EPD_C12-Pad1)") (class "Default")
      (node (ref "EPD_C12") (pin "1") (pinfunction "1_1") (pintype "passive"))
      (node (ref "J1") (pin "1") (pinfunction "1_1") (pintype "bidirectional"))
    )
    (net (code "32") (name "Net-(IC1-CT)") (class "Default")
      (node (ref "C_DELAY") (pin "1") (pinfunction "1_1") (pintype "passive"))
      (node (ref "IC1") (pin "5") (pinfunction "CT_5") (pintype "bidirectional"))
    )
    (net (code "33") (name "Net-(J2-PadA5)") (class "Default")
      (node (ref "J2") (pin "A5") (pinfunction "A5_A5") (pintype "bidirectional"))
      (node (ref "R2-USB1") (pin "2") (pinfunction "2_2") (pintype "passive"))
    )
    (net (code "34") (name "Net-(J2-PadB5)") (class "Default")
      (node (ref "J2") (pin "B5") (pinfunction "B5_B5") (pintype "bidirectional"))
      (node (ref "R2-USB") (pin "1") (pinfunction "1_1") (pintype "passive"))
    )
    (net (code "35") (name "Net-(MCP73831-PROG)") (class "Default")
      (node (ref "MCP73831") (pin "5") (pinfunction "PROG_5") (pintype "input"))
      (node (ref "R2_BAT") (pin "2") (pinfunction "2_2") (pintype "passive"))
    )
    (net (code "36") (name "Net-(MCP73831-STAT)") (class "Default")
      (node (ref "MCP73831") (pin "1") (pinfunction "STAT_1") (pintype "output"))
      (node (ref "R1_BAT") (pin "1") (pinfunction "1_1") (pintype "passive"))
    )
    (net (code "37") (name "PREVGH") (class "Default")
      (node (ref "D5") (pin "1") (pinfunction "K_1") (pintype "bidirectional"))
      (node (ref "EPD_C9") (pin "1") (pinfunction "1_1") (pintype "passive"))
      (node (ref "J1") (pin "4") (pinfunction "4_4") (pintype "bidirectional"))
    )
    (net (code "38") (name "PREVGL") (class "Default")
      (node (ref "D4") (pin "2") (pinfunction "A_2") (pintype "bidirectional"))
      (node (ref "EPD_C11") (pin "1") (pinfunction "1_1") (pintype "passive"))
      (node (ref "J1") (pin "2") (pinfunction "2_2") (pintype "bidirectional"))
    )
    (net (code "39") (name "RESE") (class "Default")
      (node (ref "J1") (pin "22") (pinfunction "22_22") (pintype "bidirectional"))
      (node (ref "Q3") (pin "2") (pinfunction "S_2") (pintype "bidirectional"))
      (node (ref "R3") (pin "1") (pinfunction "1_1") (pintype "passive"))
    )
    (net (code "40") (name "RESE'") (class "Default")
      (node (ref "R2") (pin "2") (pinfunction "2_2") (pintype "passive"))
      (node (ref "R3") (pin "2") (pinfunction "2_2") (pintype "passive"))
      (node (ref "SJ1") (pin "2") (pinfunction "2_2") (pintype "passive"))
    )
    (net (code "41") (name "RESET") (class "Default")
      (node (ref "C5") (pin "1") (pinfunction "1_1") (pintype "passive"))
      (node (ref "IC1") (pin "1") (pinfunction "VOUT_1") (pintype "bidirectional"))
      (node (ref "RESET_BUTTON") (pin "3") (pinfunction "3_3") (pintype "passive"))
      (node (ref "RESET_BUTTON") (pin "4") (pinfunction "4_4") (pintype "passive"))
      (node (ref "R_RESET") (pin "2") (pinfunction "2_2") (pintype "passive"))
      (node (ref "U2") (pin "3") (pinfunction "EN_3") (pintype "input"))
    )
    (net (code "42") (name "RTC_RST") (class "Default")
      (node (ref "U2") (pin "16") (pinfunction "IO18_16") (pintype "bidirectional"))
      (node (ref "U3") (pin "4") (pinfunction "~{RST}_4") (pintype "input"))
    )
    (net (code "43") (name "RX") (class "Default")
      (node (ref "TP2") (pin "TP") (pinfunction "TP_TP") (pintype "input"))
      (node (ref "U2") (pin "24") (pinfunction "RXD0/GPIO17_24") (pintype "bidirectional"))
    )
    (net (code "44") (name "SCK") (class "Default")
      (node (ref "D10") (pin "1") (pinfunction "1_1") (pintype "passive"))
      (node (ref "J1") (pin "12") (pinfunction "12_12") (pintype "bidirectional"))
      (node (ref "J4") (pin "P5") (pinfunction "CLK_P5") (pintype "bidirectional"))
      (node (ref "R6") (pin "1") (pinfunction "1_1") (pintype "passive"))
      (node (ref "TP8") (pin "TP") (pinfunction "TP_TP") (pintype "input"))
      (node (ref "U1") (pin "6") (pinfunction "CLK_6") (pintype "input"))
      (node (ref "U2") (pin "6") (pinfunction "IO6_6") (pintype "bidirectional"))
    )
    (net (code "45") (name "SCL") (class "Default")
      (node (ref "J3") (pin "4") (pinfunction "4_4") (pintype "passive"))
      (node (ref "R2-PINH") (pin "1") (pinfunction "1_1") (pintype "passive"))
      (node (ref "SENSOR2") (pin "4") (pinfunction "SCK_4") (pintype "input"))
      (node (ref "U2") (pin "20") (pinfunction "IO22_20") (pintype "bidirectional"))
      (node (ref "U3") (pin "16") (pinfunction "SCL_16") (pintype "input"))
      (node (ref "U4") (pin "7") (pinfunction "SCL_7") (pintype "input"))
    )
    (net (code "46") (name "SDA") (class "Default")
      (node (ref "J3") (pin "3") (pinfunction "3_3") (pintype "passive"))
      (node (ref "R1_PINH") (pin "1") (pinfunction "1_1") (pintype "passive"))
      (node (ref "SENSOR2") (pin "3") (pinfunction "SDI_3") (pintype "bidirectional"))
      (node (ref "U2") (pin "19") (pinfunction "IO21_19") (pintype "bidirectional"))
      (node (ref "U3") (pin "15") (pinfunction "SDA_15") (pintype "bidirectional"))
      (node (ref "U4") (pin "8") (pinfunction "SDA_8") (pintype "bidirectional"))
    )
    (net (code "47") (name "SRC") (class "Default")
      (node (ref "C4") (pin "2") (pinfunction "2_2") (pintype "passive"))
      (node (ref "D5") (pin "2") (pinfunction "A_2") (pintype "bidirectional"))
      (node (ref "L1") (pin "1") (pinfunction "1_1") (pintype "passive"))
      (node (ref "Q3") (pin "3") (pinfunction "D_3") (pintype "bidirectional"))
    )
    (net (code "48") (name "SS_SD") (class "Default")
      (node (ref "D8") (pin "1") (pinfunction "1_1") (pintype "passive"))
      (node (ref "J4") (pin "P2") (pinfunction "CD/DAT3_P2") (pintype "bidirectional"))
      (node (ref "R10") (pin "1") (pinfunction "1_1") (pintype "passive"))
      (node (ref "U2") (pin "4") (pinfunction "IO4_4") (pintype "bidirectional"))
    )
    (net (code "49") (name "TX") (class "Default")
      (node (ref "TP1") (pin "TP") (pinfunction "TP_TP") (pintype "input"))
      (node (ref "U2") (pin "25") (pinfunction "TXD0/GPIO16_25") (pintype "bidirectional"))
    )
    (net (code "50") (name "USB_D+") (class "Default")
      (node (ref "D1") (pin "1") (pinfunction "I/O1_1_1") (pintype "bidirectional"))
      (node (ref "U2") (pin "14") (pinfunction "IO13_14") (pintype "bidirectional"))
    )
    (net (code "51") (name "USB_D-") (class "Default")
      (node (ref "D1") (pin "3") (pinfunction "I/O2_1_3") (pintype "bidirectional"))
      (node (ref "U2") (pin "13") (pinfunction "IO12_13") (pintype "bidirectional"))
    )
    (net (code "52") (name "VBAT") (class "Default")
      (node (ref "C2_BAT") (pin "1") (pinfunction "1_1") (pintype "passive"))
      (node (ref "MCP73831") (pin "3") (pinfunction "VBAT_3") (pintype "power_in"))
      (node (ref "Q1") (pin "3") (pinfunction "D_3") (pintype "bidirectional"))
      (node (ref "TP3") (pin "TP") (pinfunction "TP_TP") (pintype "input"))
      (node (ref "U4") (pin "2") (pinfunction "CELL_2") (pintype "power_in"))
      (node (ref "U4") (pin "3") (pinfunction "VDD_3") (pintype "power_in"))
    )
    (net (code "53") (name "VBUS") (class "Default")
      (node (ref "C1_BAT") (pin "1") (pinfunction "1_1") (pintype "passive"))
      (node (ref "C4_USB") (pin "1") (pinfunction "1_1") (pintype "passive"))
      (node (ref "C5_USB") (pin "1") (pinfunction "1_1") (pintype "passive"))
      (node (ref "CHG_LED") (pin "A") (pinfunction "A_A") (pintype "passive"))
      (node (ref "D1") (pin "5") (pinfunction "VBUS_5") (pintype "bidirectional"))
      (node (ref "D2") (pin "2") (pinfunction "ANODE_2") (pintype "bidirectional"))
      (node (ref "MCP73831") (pin "4") (pinfunction "VIN_4") (pintype "power_in"))
      (node (ref "PFMF.050.1") (pin "1") (pinfunction "1_1") (pintype "passive"))
      (node (ref "Q1") (pin "1") (pinfunction "G_1") (pintype "bidirectional"))
      (node (ref "R1_PWRUSB") (pin "2") (pinfunction "2_2") (pintype "passive"))
      (node (ref "TP14") (pin "TP") (pinfunction "TP_TP") (pintype "input"))
    )
    (net (code "54") (name "VRTC") (class "Default")
      (node (ref "C10_SUPERCAP") (pin "2") (pinfunction "2_2") (pintype "passive"))
      (node (ref "C8") (pin "1") (pinfunction "1_1") (pintype "passive"))
      (node (ref "R_CAPACITOR") (pin "1") (pinfunction "1_1") (pintype "passive"))
      (node (ref "U3") (pin "14") (pinfunction "VBAT_14") (pintype "power_in"))
    )
    (net (code "55") (name "VUSB") (class "Default")
      (node (ref "J2") (pin "A4") (pinfunction "A4_A4") (pintype "bidirectional"))
      (node (ref "J2") (pin "A9") (pinfunction "A9_A9") (pintype "bidirectional"))
      (node (ref "J2") (pin "B4") (pinfunction "B4_B4") (pintype "bidirectional"))
      (node (ref "J2") (pin "B9") (pinfunction "B9_B9") (pintype "bidirectional"))
      (node (ref "PFMF.050.1") (pin "2") (pinfunction "2_2") (pintype "passive"))
    )
    (net (code "56") (name "unconnected-(IC1-NC-Pad4)") (class "Default")
      (node (ref "IC1") (pin "4") (pinfunction "NC_4") (pintype "no_connect"))
    )
    (net (code "57") (name "unconnected-(IC4-NC-Pad4)") (class "Default")
      (node (ref "IC4") (pin "4") (pinfunction "NC_4") (pintype "no_connect"))
    )
    (net (code "58") (name "unconnected-(J1-Pad18)") (class "Default")
      (node (ref "J1") (pin "18") (pinfunction "18_18") (pintype "bidirectional"))
    )
    (net (code "59") (name "unconnected-(J1-Pad19)") (class "Default")
      (node (ref "J1") (pin "19") (pinfunction "19_19") (pintype "bidirectional"))
    )
    (net (code "60") (name "unconnected-(J1-Pad24)") (class "Default")
      (node (ref "J1") (pin "24") (pinfunction "24_24") (pintype "bidirectional"))
    )
    (net (code "61") (name "unconnected-(J2-PadA8)") (class "Default")
      (node (ref "J2") (pin "A8") (pinfunction "A8_A8") (pintype "bidirectional"))
    )
    (net (code "62") (name "unconnected-(J2-PadB8)") (class "Default")
      (node (ref "J2") (pin "B8") (pinfunction "B8_B8") (pintype "bidirectional"))
    )
    (net (code "63") (name "unconnected-(J4-DAT1-PadP8)") (class "Default")
      (node (ref "J4") (pin "P8") (pinfunction "DAT1_P8") (pintype "bidirectional"))
    )
    (net (code "64") (name "unconnected-(J4-DAT2-PadP1)") (class "Default")
      (node (ref "J4") (pin "P1") (pinfunction "DAT2_P1") (pintype "bidirectional"))
    )
    (net (code "65") (name "unconnected-(J4-DETECTION_1-PadS1)") (class "Default")
      (node (ref "J4") (pin "S1") (pinfunction "DETECTION_1_S1") (pintype "bidirectional"))
    )
    (net (code "66") (name "unconnected-(J4-DETECTION_2-PadS2)") (class "Default")
      (node (ref "J4") (pin "S2") (pinfunction "DETECTION_2_S2") (pintype "bidirectional"))
    )
    (net (code "67") (name "unconnected-(U2-NC-Pad22)") (class "Default")
      (node (ref "U2") (pin "22") (pinfunction "NC_22") (pintype "no_connect"))
    )
    (net (code "68") (name "unconnected-(U4-~{ALERT}-Pad5)") (class "Default")
      (node (ref "U4") (pin "5") (pinfunction "~{ALERT}_5") (pintype "output"))
    )
  )
)
